# Schematic_v72.net
KiCad netlist of a schematic drawn in EAGLE
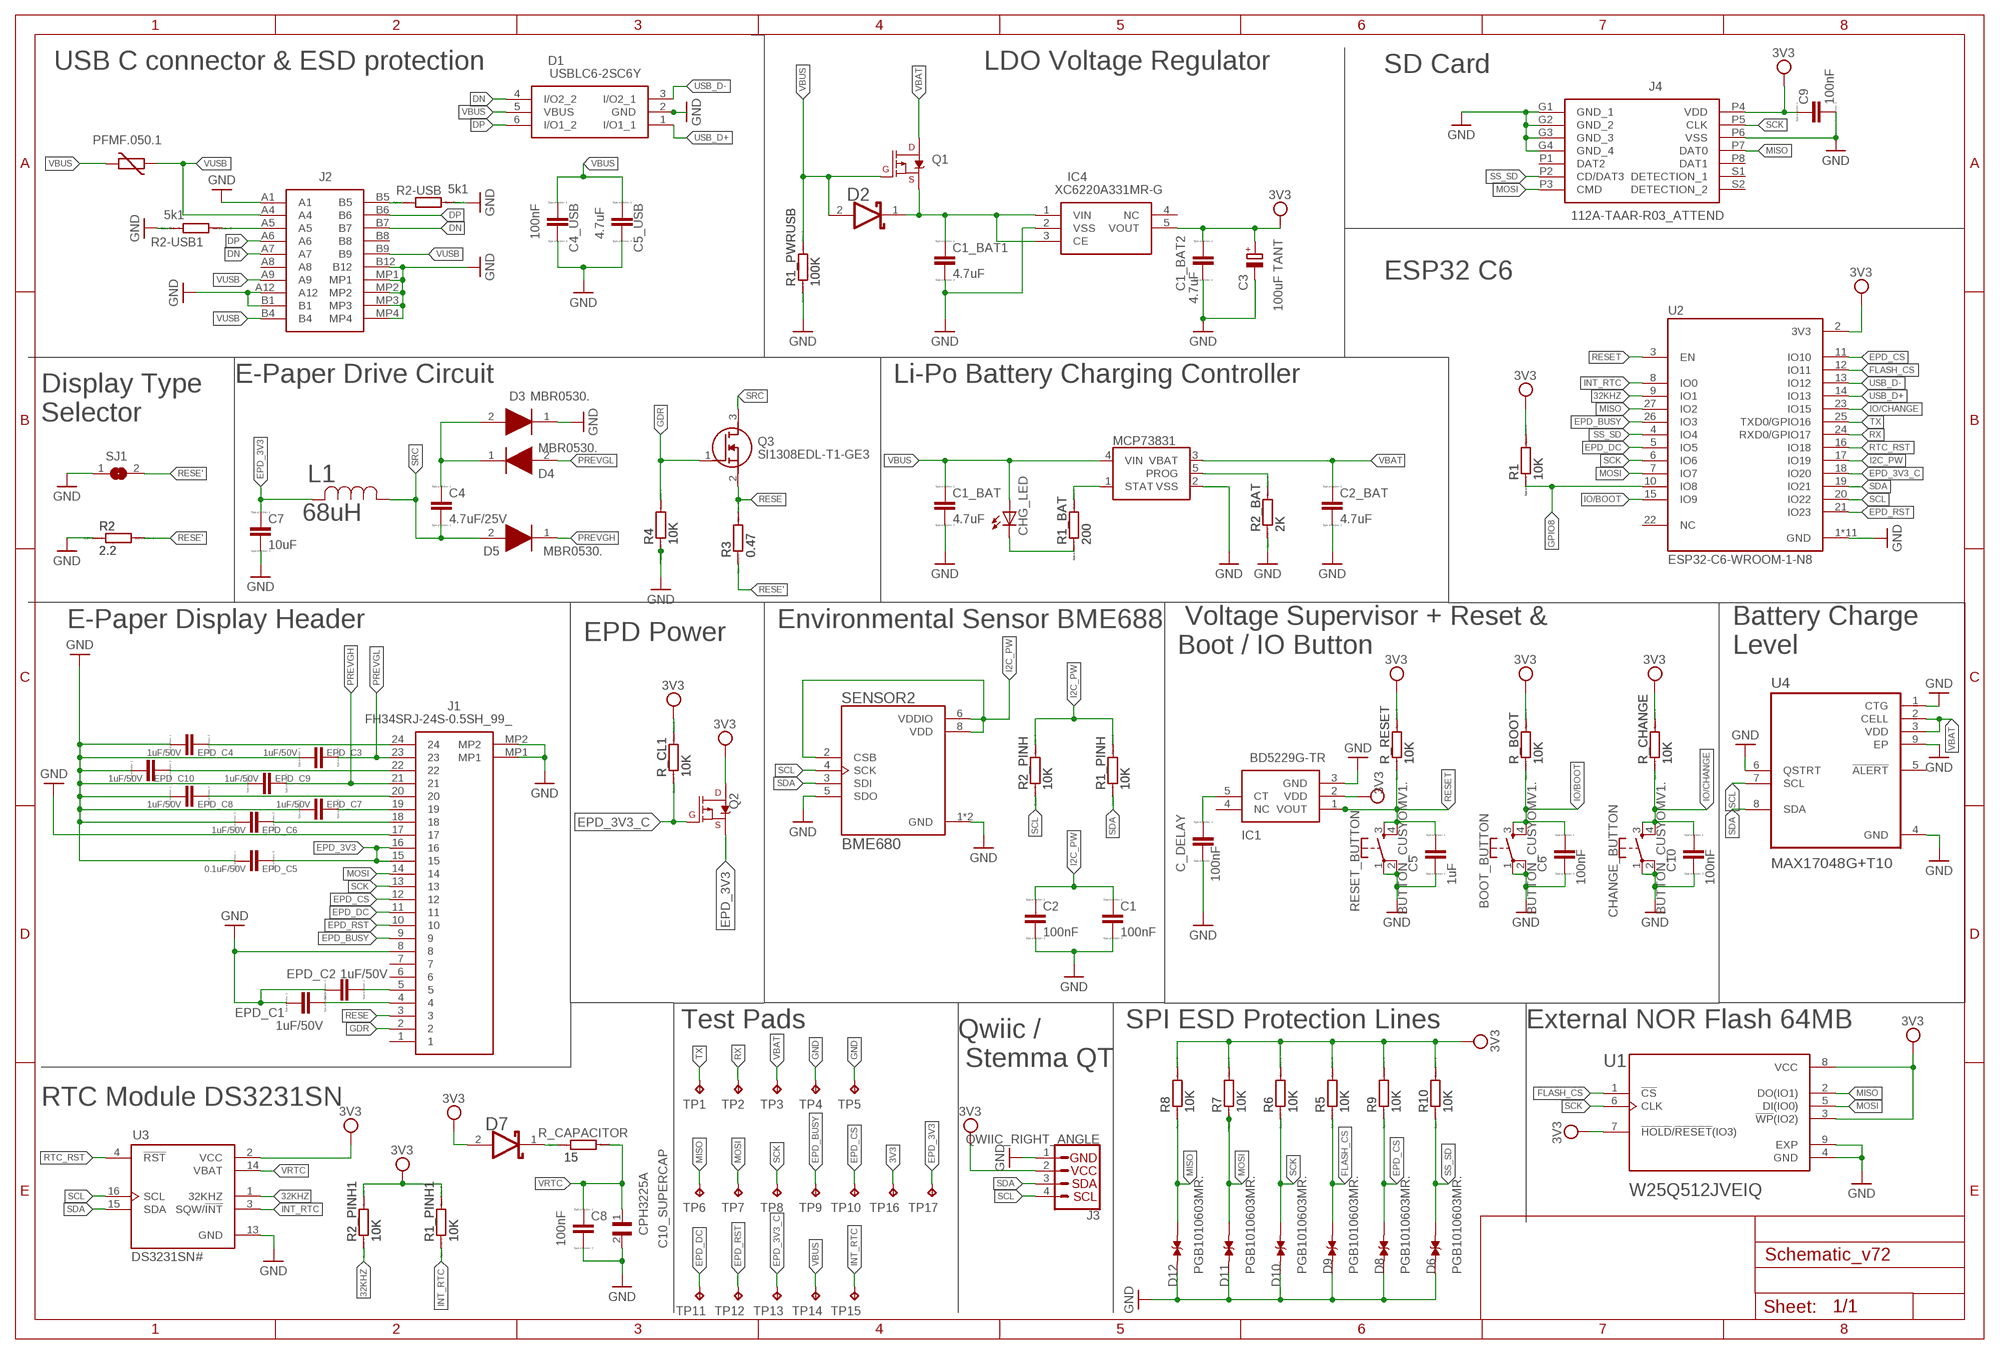
[diagram p0: schematic, sheet 1]

(export (version "E")
  (design (tool "Eeschema 10.0.6"))
  (components
    (comp (ref "BOOT_BUTTON")
      (value "BUTTON_CUSYOMV1.")
      (footprint "eagle-import:MYBUTTON")
      (libsource (lib "eagle-import") (part "BUTTON_CUSYOMV1."))
    )
    (comp (ref "C1")
      (value "100nF")
      (footprint "eagle-import:EAGLE-LTSPICE_C0402")
      (libsource (lib "eagle-import") (part "EAGLE-LTSPICE_C"))
    )
    (comp (ref "C1_BAT")
      (value "4.7uF")
      (footprint "eagle-import:EAGLE-LTSPICE_C0402")
      (libsource (lib "eagle-import") (part "EAGLE-LTSPICE_C"))
    )
    (comp (ref "C1_BAT1")
      (value "4.7uF")
      (footprint "eagle-import:EAGLE-LTSPICE_C0402")
      (libsource (lib "eagle-import") (part "EAGLE-LTSPICE_C"))
    )
    (comp (ref "C1_BAT2")
      (value "4.7uF")
      (footprint "eagle-import:EAGLE-LTSPICE_C0402")
      (libsource (lib "eagle-import") (part "EAGLE-LTSPICE_C"))
    )
    (comp (ref "C2")
      (value "100nF")
      (footprint "eagle-import:EAGLE-LTSPICE_C0402")
      (libsource (lib "eagle-import") (part "EAGLE-LTSPICE_C"))
    )
    (comp (ref "C2_BAT")
      (value "4.7uF")
      (footprint "eagle-import:EAGLE-LTSPICE_C0402")
      (libsource (lib "eagle-import") (part "EAGLE-LTSPICE_C"))
    )
    (comp (ref "C3")
      (value "100uF TANT")
      (footprint "eagle-import:RCL_CT3528")
      (libsource (lib "eagle-import") (part "RCL_CPOL-EUCT3528"))
    )
    (comp (ref "C4")
      (value "4.7uF/25V")
      (footprint "eagle-import:EAGLE-LTSPICE_C0402")
      (libsource (lib "eagle-import") (part "EAGLE-LTSPICE_C"))
    )
    (comp (ref "C4_USB")
      (value "100nF")
      (footprint "eagle-import:EAGLE-LTSPICE_C0402")
      (libsource (lib "eagle-import") (part "EAGLE-LTSPICE_C"))
    )
    (comp (ref "C5")
      (value "1uF")
      (footprint "eagle-import:EAGLE-LTSPICE_C0402")
      (libsource (lib "eagle-import") (part "EAGLE-LTSPICE_C"))
    )
    (comp (ref "C5_USB")
      (value "4.7uF")
      (footprint "eagle-import:EAGLE-LTSPICE_C0402")
      (libsource (lib "eagle-import") (part "EAGLE-LTSPICE_C"))
    )
    (comp (ref "C6")
      (value "100nF")
      (footprint "eagle-import:EAGLE-LTSPICE_C0402")
      (libsource (lib "eagle-import") (part "EAGLE-LTSPICE_C"))
    )
    (comp (ref "C7")
      (value "10uF")
      (footprint "eagle-import:EAGLE-LTSPICE_C0402")
      (libsource (lib "eagle-import") (part "EAGLE-LTSPICE_C"))
    )
    (comp (ref "C8")
      (value "100nF")
      (footprint "eagle-import:EAGLE-LTSPICE_C0402")
      (libsource (lib "eagle-import") (part "EAGLE-LTSPICE_C"))
    )
    (comp (ref "C9")
      (value "100nF")
      (footprint "eagle-import:EAGLE-LTSPICE_C0402")
      (libsource (lib "eagle-import") (part "EAGLE-LTSPICE_C"))
    )
    (comp (ref "C10")
      (value "100nF")
      (footprint "eagle-import:EAGLE-LTSPICE_C0402")
      (libsource (lib "eagle-import") (part "EAGLE-LTSPICE_C"))
    )
    (comp (ref "C10_SUPERCAP")
      (value "CPH3225A")
      (footprint "eagle-import:CAPCP3225X100N")
      (fields (field (name "MF") "Seiko Instruments"))
      (libsource (lib "eagle-import") (part "CPH3225A"))
    )
    (comp (ref "CHANGE_BUTTON")
      (value "BUTTON_CUSYOMV1.")
      (footprint "eagle-import:MYBUTTON")
      (libsource (lib "eagle-import") (part "BUTTON_CUSYOMV1."))
    )
    (comp (ref "CHG_LED")
      (value "ADAFRUIT_LEDCHIP-LED0603")
      (footprint "eagle-import:ADAFRUIT_CHIP-LED0603")
      (libsource (lib "eagle-import") (part "ADAFRUIT_LEDCHIP-LED0603"))
    )
    (comp (ref "C_DELAY")
      (value "100nF")
      (footprint "eagle-import:EAGLE-LTSPICE_C0402")
      (libsource (lib "eagle-import") (part "EAGLE-LTSPICE_C"))
    )
    (comp (ref "D1")
      (value "USBLC6-2SC6Y")
      (footprint "eagle-import:SOT95P280X145-6N")
      (fields (field (name "MF") "STMicroelectronics"))
      (libsource (lib "eagle-import") (part "USBLC6-2SC6Y"))
    )
    (comp (ref "D2")
      (value "ESP32_WROVER_AVX---SD0805S020S1R0_AVX_SD0805S020S1R0_0_0")
      (footprint "eagle-import:ESP32_WROVER_AVX---SD0805S020S1R0_AVX_SD0805S020S1R0_0")
      (libsource (lib "eagle-import") (part "ESP32_WROVER_AVX---SD0805S020S1R0_AVX_SD0805S020S1R0_0_0"))
    )
    (comp (ref "D3")
      (value "MBR0530.")
      (footprint "eagle-import:SOD3716X135N")
      (libsource (lib "eagle-import") (part "MBR0530."))
    )
    (comp (ref "D4")
      (value "MBR0530.")
      (footprint "eagle-import:SOD3716X135N")
      (libsource (lib "eagle-import") (part "MBR0530."))
    )
    (comp (ref "D5")
      (value "MBR0530.")
      (footprint "eagle-import:SOD3716X135N")
      (libsource (lib "eagle-import") (part "MBR0530."))
    )
    (comp (ref "D6")
      (value "PGB1010603MR.")
      (footprint "eagle-import:DIOC1608X36N")
      (libsource (lib "eagle-import") (part "PGB1010603MR."))
    )
    (comp (ref "D7")
      (value "SD0805S020S1R0")
      (footprint "eagle-import:ESP32_WROVER_AVX---SD0805S020S1R0_AVX_SD0805S020S1R0_0")
      (libsource (lib "eagle-import") (part "ESP32_WROVER_AVX---SD0805S020S1R0_AVX_SD0805S020S1R0_0_0"))
    )
    (comp (ref "D8")
      (value "PGB1010603MR.")
      (footprint "eagle-import:DIOC1608X36N")
      (libsource (lib "eagle-import") (part "PGB1010603MR."))
    )
    (comp (ref "D9")
      (value "PGB1010603MR.")
      (footprint "eagle-import:DIOC1608X36N")
      (libsource (lib "eagle-import") (part "PGB1010603MR."))
    )
    (comp (ref "D10")
      (value "PGB1010603MR.")
      (footprint "eagle-import:DIOC1608X36N")
      (libsource (lib "eagle-import") (part "PGB1010603MR."))
    )
    (comp (ref "D11")
      (value "PGB1010603MR.")
      (footprint "eagle-import:DIOC1608X36N")
      (libsource (lib "eagle-import") (part "PGB1010603MR."))
    )
    (comp (ref "D12")
      (value "PGB1010603MR.")
      (footprint "eagle-import:DIOC1608X36N")
      (libsource (lib "eagle-import") (part "PGB1010603MR."))
    )
    (comp (ref "EPD_C1")
      (value "1uF/50V")
      (footprint "eagle-import:EAGLE-LTSPICE_C0402")
      (libsource (lib "eagle-import") (part "EAGLE-LTSPICE_C"))
    )
    (comp (ref "EPD_C2")
      (value "1uF/50V")
      (footprint "eagle-import:EAGLE-LTSPICE_C0402")
      (libsource (lib "eagle-import") (part "EAGLE-LTSPICE_C"))
    )
    (comp (ref "EPD_C3")
      (value "1uF/50V")
      (footprint "eagle-import:EAGLE-LTSPICE_C0402")
      (libsource (lib "eagle-import") (part "EAGLE-LTSPICE_C"))
    )
    (comp (ref "EPD_C4")
      (value "1uF/50V")
      (footprint "eagle-import:EAGLE-LTSPICE_C0402")
      (libsource (lib "eagle-import") (part "EAGLE-LTSPICE_C"))
    )
    (comp (ref "EPD_C5")
      (value "0.1uF/50V")
      (footprint "eagle-import:EAGLE-LTSPICE_C0402")
      (libsource (lib "eagle-import") (part "EAGLE-LTSPICE_C"))
    )
    (comp (ref "EPD_C6")
      (value "1uF/50V")
      (footprint "eagle-import:EAGLE-LTSPICE_C0402")
      (libsource (lib "eagle-import") (part "EAGLE-LTSPICE_C"))
    )
    (comp (ref "EPD_C7")
      (value "1uF/50V")
      (footprint "eagle-import:EAGLE-LTSPICE_C0402")
      (libsource (lib "eagle-import") (part "EAGLE-LTSPICE_C"))
    )
    (comp (ref "EPD_C8")
      (value "1uF/50V")
      (footprint "eagle-import:EAGLE-LTSPICE_C0402")
      (libsource (lib "eagle-import") (part "EAGLE-LTSPICE_C"))
    )
    (comp (ref "EPD_C9")
      (value "1uF/50V")
      (footprint "eagle-import:EAGLE-LTSPICE_C0402")
      (libsource (lib "eagle-import") (part "EAGLE-LTSPICE_C"))
    )
    (comp (ref "EPD_C10")
      (value "1uF/50V")
      (footprint "eagle-import:EAGLE-LTSPICE_C0402")
      (libsource (lib "eagle-import") (part "EAGLE-LTSPICE_C"))
    )
    (comp (ref "IC1")
      (value "BD5229G-TR")
      (footprint "eagle-import:SOT95P280X125-5N")
      (fields (field (name "MOUSER_PART_NUMBER") "755-BD5229G-TR"))
      (libsource (lib "eagle-import") (part "BD5229G-TR"))
    )
    (comp (ref "IC4")
      (value "XC6220A331MR-G")
      (footprint "eagle-import:SOT95P280X120-5N")
      (fields (field (name "MOUSER_PART_NUMBER") "865-XC6220A331MR-G"))
      (libsource (lib "eagle-import") (part "XC6220A331MR-G"))
    )
    (comp (ref "J1")
      (value "FH34SRJ-24S-0.5SH_99_")
      (footprint "eagle-import:FH34SRJ24S05SH99")
      (fields
        (field (name "MANUFACTURER_PART_NUMBER") "FH34SRJ-24S-0.5SH(99)")
        (field (name "MOUSER_PART_NUMBER") "798-FH34SRJ24S05SH99")
      )
      (libsource (lib "eagle-import") (part "FH34SRJ-24S-0.5SH_99_"))
    )
    (comp (ref "J2")
      (value "SAMACSYS_PARTS_USB4110-GF-A")
      (footprint "eagle-import:SAMACSYS_PARTS_USB4110GFA")
      (fields
        (field (name "MANUFACTURER_PART_NUMBER") "USB4110-GF-A")
        (field (name "MOUSER_PART_NUMBER") "640-USB4110-GF-A")
      )
      (libsource (lib "eagle-import") (part "SAMACSYS_PARTS_USB4110-GF-A"))
    )
    (comp (ref "J3")
      (value "QWIIC_RIGHT_ANGLE")
      (footprint "eagle-import:JST04_1MM_RA")
      (libsource (lib "eagle-import") (part "QWIIC_CONNECTORJS-1MM"))
    )
    (comp (ref "J4")
      (value "112A-TAAR-R03_ATTEND")
      (footprint "eagle-import:112ATAARR03ATTEND")
      (fields (field (name "MANUFACTURER_PART_NUMBER") "112A-TAAR-R03 ATTEND"))
      (libsource (lib "eagle-import") (part "112A-TAAR-R03_ATTEND"))
    )
    (comp (ref "L1")
      (value "68uH")
      (footprint "eagle-import:IND_4828-WE-TPC_WRE")
      (fields
        (field (name "MANUFACTURER_PART_NUMBER") "744043680")
        (field (name "COPYRIGHT") "Copyright (C) 2024 Ultra Librarian. All rights reserved.")
      )
      (libsource (lib "eagle-import") (part "744043680IND_4828-WE-TPC_WRE"))
    )
    (comp (ref "MCP73831")
      (value "ESP32_WROVER_SPARKFUN-IC-POWER_MCP73831")
      (footprint "eagle-import:ESP32_WROVER_SPARKFUN-IC-POWER_SOT23-5")
      (libsource (lib "eagle-import") (part "ESP32_WROVER_SPARKFUN-IC-POWER_MCP73831"))
    )
    (comp (ref "PFMF.050.1")
      (value "ESP32C6_VARISTORCN1812")
      (footprint "eagle-import:ESP32C6_VARISTOR_CT_CN1812")
      (libsource (lib "eagle-import") (part "ESP32C6_VARISTORCN1812"))
    )
    (comp (ref "Q1")
      (value "20V/4.2A/52mΩ/1.4W")
      (footprint "eagle-import:ESP32_WROVER_SPARKFUN-DISCRETESEMI_SOT23-3")
      (libsource (lib "eagle-import") (part "ESP32_WROVER_SPARKFUN-DISCRETESEMI_MOSFET_PCH"))
    )
    (comp (ref "Q2")
      (value "20V/4.2A/52mΩ/1.4W")
      (footprint "eagle-import:ESP32_WROVER_SPARKFUN-DISCRETESEMI_SOT23-3")
      (libsource (lib "eagle-import") (part "ESP32_WROVER_SPARKFUN-DISCRETESEMI_MOSFET_PCH"))
    )
    (comp (ref "Q3")
      (value "SI1308EDL-T1-GE3")
      (footprint "eagle-import:SOT65P210X110-3N")
      (fields (field (name "MF") "Vishay Siliconix"))
      (libsource (lib "eagle-import") (part "SI1308EDL-T1-GE3"))
    )
    (comp (ref "R1")
      (value "10K")
      (footprint "eagle-import:ESP32_WROVER_EAGLE-LTSPICE_R0402")
      (libsource (lib "eagle-import") (part "ESP32_WROVER_EAGLE-LTSPICE_R"))
    )
    (comp (ref "R1_BAT")
      (value "200")
      (footprint "eagle-import:ESP32_WROVER_EAGLE-LTSPICE_R0402")
      (libsource (lib "eagle-import") (part "ESP32_WROVER_EAGLE-LTSPICE_R"))
    )
    (comp (ref "R1_PINH")
      (value "10K")
      (footprint "eagle-import:ESP32_WROVER_EAGLE-LTSPICE_R0402")
      (libsource (lib "eagle-import") (part "ESP32_WROVER_EAGLE-LTSPICE_R"))
    )
    (comp (ref "R1_PINH1")
      (value "10K")
      (footprint "eagle-import:ESP32_WROVER_EAGLE-LTSPICE_R0402")
      (libsource (lib "eagle-import") (part "ESP32_WROVER_EAGLE-LTSPICE_R"))
    )
    (comp (ref "R1_PWRUSB")
      (value "100K")
      (footprint "eagle-import:ESP32_WROVER_EAGLE-LTSPICE_R0402")
      (libsource (lib "eagle-import") (part "ESP32_WROVER_EAGLE-LTSPICE_R"))
    )
    (comp (ref "R2")
      (value "2.2")
      (footprint "eagle-import:ESP32_WROVER_EAGLE-LTSPICE_R0402")
      (libsource (lib "eagle-import") (part "ESP32_WROVER_EAGLE-LTSPICE_R"))
    )
    (comp (ref "R2-USB")
      (value "5k1")
      (footprint "eagle-import:ESP32_WROVER_EAGLE-LTSPICE_R0402")
      (libsource (lib "eagle-import") (part "ESP32_WROVER_EAGLE-LTSPICE_R"))
    )
    (comp (ref "R2-USB1")
      (value "5k1")
      (footprint "eagle-import:ESP32_WROVER_EAGLE-LTSPICE_R0402")
      (libsource (lib "eagle-import") (part "ESP32_WROVER_EAGLE-LTSPICE_R"))
    )
    (comp (ref "R2_BAT")
      (value "2K")
      (footprint "eagle-import:ESP32_WROVER_EAGLE-LTSPICE_R0402")
      (libsource (lib "eagle-import") (part "ESP32_WROVER_EAGLE-LTSPICE_R"))
    )
    (comp (ref "R2_PINH")
      (value "10K")
      (footprint "eagle-import:ESP32_WROVER_EAGLE-LTSPICE_R0402")
      (libsource (lib "eagle-import") (part "ESP32_WROVER_EAGLE-LTSPICE_R"))
    )
    (comp (ref "R2_PINH1")
      (value "10K")
      (footprint "eagle-import:ESP32_WROVER_EAGLE-LTSPICE_R0402")
      (libsource (lib "eagle-import") (part "ESP32_WROVER_EAGLE-LTSPICE_R"))
    )
    (comp (ref "R3")
      (value "0.47")
      (footprint "eagle-import:ESP32_WROVER_EAGLE-LTSPICE_R0402")
      (libsource (lib "eagle-import") (part "ESP32_WROVER_EAGLE-LTSPICE_R"))
    )
    (comp (ref "R4")
      (value "10K")
      (footprint "eagle-import:ESP32_WROVER_EAGLE-LTSPICE_R0402")
      (libsource (lib "eagle-import") (part "ESP32_WROVER_EAGLE-LTSPICE_R"))
    )
    (comp (ref "R5")
      (value "10K")
      (footprint "eagle-import:ESP32_WROVER_EAGLE-LTSPICE_R0402")
      (libsource (lib "eagle-import") (part "ESP32_WROVER_EAGLE-LTSPICE_R"))
    )
    (comp (ref "R6")
      (value "10K")
      (footprint "eagle-import:ESP32_WROVER_EAGLE-LTSPICE_R0402")
      (libsource (lib "eagle-import") (part "ESP32_WROVER_EAGLE-LTSPICE_R"))
    )
    (comp (ref "R7")
      (value "10K")
      (footprint "eagle-import:ESP32_WROVER_EAGLE-LTSPICE_R0402")
      (libsource (lib "eagle-import") (part "ESP32_WROVER_EAGLE-LTSPICE_R"))
    )
    (comp (ref "R8")
      (value "10K")
      (footprint "eagle-import:ESP32_WROVER_EAGLE-LTSPICE_R0402")
      (libsource (lib "eagle-import") (part "ESP32_WROVER_EAGLE-LTSPICE_R"))
    )
    (comp (ref "R9")
      (value "10K")
      (footprint "eagle-import:ESP32_WROVER_EAGLE-LTSPICE_R0402")
      (libsource (lib "eagle-import") (part "ESP32_WROVER_EAGLE-LTSPICE_R"))
    )
    (comp (ref "R10")
      (value "10K")
      (footprint "eagle-import:ESP32_WROVER_EAGLE-LTSPICE_R0402")
      (libsource (lib "eagle-import") (part "ESP32_WROVER_EAGLE-LTSPICE_R"))
    )
    (comp (ref "RESET_BUTTON")
      (value "BUTTON_CUSYOMV1.")
      (footprint "eagle-import:MYBUTTON")
      (libsource (lib "eagle-import") (part "BUTTON_CUSYOMV1."))
    )
    (comp (ref "R_BOOT")
      (value "10K")
      (footprint "eagle-import:ESP32_WROVER_EAGLE-LTSPICE_R0402")
      (libsource (lib "eagle-import") (part "ESP32_WROVER_EAGLE-LTSPICE_R"))
    )
    (comp (ref "R_CAPACITOR")
      (value "15")
      (footprint "eagle-import:ESP32_WROVER_EAGLE-LTSPICE_R0402")
      (libsource (lib "eagle-import") (part "ESP32_WROVER_EAGLE-LTSPICE_R"))
    )
    (comp (ref "R_CHANGE")
      (value "10K")
      (footprint "eagle-import:ESP32_WROVER_EAGLE-LTSPICE_R0402")
      (libsource (lib "eagle-import") (part "ESP32_WROVER_EAGLE-LTSPICE_R"))
    )
    (comp (ref "R_CL1")
      (value "10K")
      (footprint "eagle-import:ESP32_WROVER_EAGLE-LTSPICE_R0402")
      (libsource (lib "eagle-import") (part "ESP32_WROVER_EAGLE-LTSPICE_R"))
    )
    (comp (ref "R_RESET")
      (value "10K")
      (footprint "eagle-import:ESP32_WROVER_EAGLE-LTSPICE_R0402")
      (libsource (lib "eagle-import") (part "ESP32_WROVER_EAGLE-LTSPICE_R"))
    )
    (comp (ref "SENSOR2")
      (value "BME680")
      (footprint "eagle-import:ESP32_WROVER_BME680_PSON80P300X300X100-8N")
      (fields (field (name "MF") "Bosch Sensortec"))
      (libsource (lib "eagle-import") (part "ESP32_WROVER_BME680_BME680"))
    )
    (comp (ref "SJ1") (value "SJ") (footprint "eagle-import:SJ") (libsource (lib "eagle-import") (part "SJ")))
    (comp (ref "TP1")
      (value "TX")
      (footprint "eagle-import:TP20R")
      (libsource (lib "eagle-import") (part "TP"))
    )
    (comp (ref "TP2")
      (value "RX")
      (footprint "eagle-import:TP20R")
      (libsource (lib "eagle-import") (part "TP"))
    )
    (comp (ref "TP3")
      (value "VBAT")
      (footprint "eagle-import:TP20R")
      (libsource (lib "eagle-import") (part "TP"))
    )
    (comp (ref "TP4")
      (value "GND")
      (footprint "eagle-import:TP20R")
      (libsource (lib "eagle-import") (part "TP"))
    )
    (comp (ref "TP5")
      (value "GND")
      (footprint "eagle-import:TP20R")
      (libsource (lib "eagle-import") (part "TP"))
    )
    (comp (ref "TP6")
      (value "MISO")
      (footprint "eagle-import:TP20R")
      (libsource (lib "eagle-import") (part "TP"))
    )
    (comp (ref "TP7")
      (value "MOSI")
      (footprint "eagle-import:TP20R")
      (libsource (lib "eagle-import") (part "TP"))
    )
    (comp (ref "TP8")
      (value "SCK")
      (footprint "eagle-import:TP20R")
      (libsource (lib "eagle-import") (part "TP"))
    )
    (comp (ref "TP9")
      (value "EPD_BUSY")
      (footprint "eagle-import:TP20R")
      (libsource (lib "eagle-import") (part "TP"))
    )
    (comp (ref "TP10")
      (value "EPD_CS")
      (footprint "eagle-import:TP20R")
      (libsource (lib "eagle-import") (part "TP"))
    )
    (comp (ref "TP11")
      (value "EPD_DC")
      (footprint "eagle-import:TP20R")
      (libsource (lib "eagle-import") (part "TP"))
    )
    (comp (ref "TP12")
      (value "EPD_RST")
      (footprint "eagle-import:TP20R")
      (libsource (lib "eagle-import") (part "TP"))
    )
    (comp (ref "TP13")
      (value "EPD_3V3_C")
      (footprint "eagle-import:TP20R")
      (libsource (lib "eagle-import") (part "TP"))
    )
    (comp (ref "TP14")
      (value "VBUS")
      (footprint "eagle-import:TP20R")
      (libsource (lib "eagle-import") (part "TP"))
    )
    (comp (ref "TP15")
      (value "INT_RTC")
      (footprint "eagle-import:TP20R")
      (libsource (lib "eagle-import") (part "TP"))
    )
    (comp (ref "TP16")
      (value "3V3")
      (footprint "eagle-import:TP20R")
      (libsource (lib "eagle-import") (part "TP"))
    )
    (comp (ref "TP17")
      (value "EPD_3V3")
      (footprint "eagle-import:TP20R")
      (libsource (lib "eagle-import") (part "TP"))
    )
    (comp (ref "U1")
      (value "W25Q512JVEIQ")
      (footprint "eagle-import:SON127P600X800X80-9N")
      (fields (field (name "MF") "Winbond Electronics"))
      (libsource (lib "eagle-import") (part "W25Q512JVEIQ"))
    )
    (comp (ref "U2")
      (value "ESP32-C6-WROOM-1-N8")
      (footprint "eagle-import:XCVR_ESP32-C6-WROOM-1-N8")
      (fields (field (name "MF") "Espressif Systems"))
      (libsource (lib "eagle-import") (part "ESP32-C6-WROOM-1-N8"))
    )
    (comp (ref "U3")
      (value "DS3231SN#")
      (footprint "eagle-import:SOIC127P1032X265-16N")
      (fields (field (name "MF") "Analog Devices"))
      (libsource (lib "eagle-import") (part "DS3231SN#"))
    )
    (comp (ref "U4")
      (value "MAX17048G+T10")
      (footprint "eagle-import:SON50P200X200X80-9N")
      (fields (field (name "MF") "Analog Devices"))
      (libsource (lib "eagle-import") (part "MAX17048G+T10"))
    )
  )
  (nets
    (net (code "1") (name "3V3") (class "Default")
      (node (ref "C1_BAT2") (pin "1") (pinfunction "1_1") (pintype "passive"))
      (node (ref "C3") (pin "+") (pinfunction "+_+") (pintype "passive"))
      (node (ref "C9") (pin "1") (pinfunction "1_1") (pintype "passive"))
      (node (ref "D7") (pin "2") (pinfunction "ANODE_2") (pintype "bidirectional"))
      (node (ref "IC1") (pin "2") (pinfunction "VDD_2") (pintype "bidirectional"))
      (node (ref "IC4") (pin "5") (pinfunction "VOUT_5") (pintype "bidirectional"))
      (node (ref "J3") (pin "2") (pinfunction "2_2") (pintype "power_in"))
      (node (ref "J4") (pin "P4") (pinfunction "VDD_P4") (pintype "bidirectional"))
      (node (ref "Q2") (pin "3") (pinfunction "D_3") (pintype "bidirectional"))
      (node (ref "R1") (pin "2") (pinfunction "2_2") (pintype "passive"))
      (node (ref "R10") (pin "2") (pinfunction "2_2") (pintype "passive"))
      (node (ref "R1_PINH1") (pin "2") (pinfunction "2_2") (pintype "passive"))
      (node (ref "R2_PINH1") (pin "2") (pinfunction "2_2") (pintype "passive"))
      (node (ref "R5") (pin "2") (pinfunction "2_2") (pintype "passive"))
      (node (ref "R6") (pin "2") (pinfunction "2_2") (pintype "passive"))
      (node (ref "R7") (pin "2") (pinfunction "2_2") (pintype "passive"))
      (node (ref "R8") (pin "2") (pinfunction "2_2") (pintype "passive"))
      (node (ref "R9") (pin "2") (pinfunction "2_2") (pintype "passive"))
      (node (ref "R_BOOT") (pin "2") (pinfunction "2_2") (pintype "passive"))
      (node (ref "R_CHANGE") (pin "2") (pinfunction "2_2") (pintype "passive"))
      (node (ref "R_CL1") (pin "2") (pinfunction "2_2") (pintype "passive"))
      (node (ref "R_RESET") (pin "2") (pinfunction "2_2") (pintype "passive"))
      (node (ref "TP16") (pin "TP") (pinfunction "TP_TP") (pintype "input"))
      (node (ref "U1") (pin "3") (pinfunction "~{WP}(IO2)_3") (pintype "bidirectional"))
      (node (ref "U1") (pin "7") (pinfunction "~{HOLD}/~{RESET}(IO3)_7") (pintype "bidirectional"))
      (node (ref "U1") (pin "8") (pinfunction "VCC_8") (pintype "power_in"))
      (node (ref "U2") (pin "2") (pinfunction "3V3_2") (pintype "power_in"))
      (node (ref "U3") (pin "2") (pinfunction "VCC_2") (pintype "power_in"))
    )
    (net (code "2") (name "32KHZ") (class "Default")
      (node (ref "R2_PINH1") (pin "1") (pinfunction "1_1") (pintype "passive"))
      (node (ref "U2") (pin "9") (pinfunction "IO1_9") (pintype "bidirectional"))
      (node (ref "U3") (pin "1") (pinfunction "32KHZ_1") (pintype "output"))
    )
    (net (code "3") (name "DN") (class "Default")
      (node (ref "D1") (pin "4") (pinfunction "I/O2_2_4") (pintype "bidirectional"))
      (node (ref "J2") (pin "A7") (pinfunction "A7_A7") (pintype "bidirectional"))
      (node (ref "J2") (pin "B7") (pinfunction "B7_B7") (pintype "bidirectional"))
    )
    (net (code "4") (name "DP") (class "Default")
      (node (ref "D1") (pin "6") (pinfunction "I/O1_2_6") (pintype "bidirectional"))
      (node (ref "J2") (pin "A6") (pinfunction "A6_A6") (pintype "bidirectional"))
      (node (ref "J2") (pin "B6") (pinfunction "B6_B6") (pintype "bidirectional"))
    )
    (net (code "5") (name "EPD_3V3") (class "Default")
      (node (ref "C7") (pin "1") (pinfunction "1_1") (pintype "passive"))
      (node (ref "EPD_C5") (pin "2") (pinfunction "2_2") (pintype "passive"))
      (node (ref "J1") (pin "15") (pinfunction "15_15") (pintype "bidirectional"))
      (node (ref "J1") (pin "16") (pinfunction "16_16") (pintype "bidirectional"))
      (node (ref "L1") (pin "2") (pinfunction "2_2") (pintype "passive"))
      (node (ref "Q2") (pin "2") (pinfunction "S_2") (pintype "bidirectional"))
      (node (ref "TP17") (pin "TP") (pinfunction "TP_TP") (pintype "input"))
    )
    (net (code "6") (name "EPD_3V3_C") (class "Default")
      (node (ref "Q2") (pin "1") (pinfunction "G_1") (pintype "bidirectional"))
      (node (ref "R_CL1") (pin "1") (pinfunction "1_1") (pintype "passive"))
      (node (ref "TP13") (pin "TP") (pinfunction "TP_TP") (pintype "input"))
      (node (ref "U2") (pin "18") (pinfunction "IO20_18") (pintype "bidirectional"))
    )
    (net (code "7") (name "EPD_BUSY") (class "Default")
      (node (ref "J1") (pin "9") (pinfunction "9_9") (pintype "bidirectional"))
      (node (ref "TP9") (pin "TP") (pinfunction "TP_TP") (pintype "input"))
      (node (ref "U2") (pin "26") (pinfunction "IO3_26") (pintype "bidirectional"))
    )
    (net (code "8") (name "EPD_CS") (class "Default")
      (node (ref "D8") (pin "2") (pinfunction "2_2") (pintype "passive"))
      (node (ref "J1") (pin "12") (pinfunction "12_12") (pintype "bidirectional"))
      (node (ref "R9") (pin "1") (pinfunction "1_1") (pintype "passive"))
      (node (ref "TP10") (pin "TP") (pinfunction "TP_TP") (pintype "input"))
      (node (ref "U2") (pin "11") (pinfunction "IO10_11") (pintype "bidirectional"))
    )
    (net (code "9") (name "EPD_DC") (class "Default")
      (node (ref "J1") (pin "11") (pinfunction "11_11") (pintype "bidirectional"))
      (node (ref "TP11") (pin "TP") (pinfunction "TP_TP") (pintype "input"))
      (node (ref "U2") (pin "5") (pinfunction "IO5_5") (pintype "bidirectional"))
    )
    (net (code "10") (name "EPD_RST") (class "Default")
      (node (ref "J1") (pin "10") (pinfunction "10_10") (pintype "bidirectional"))
      (node (ref "TP12") (pin "TP") (pinfunction "TP_TP") (pintype "input"))
      (node (ref "U2") (pin "21") (pinfunction "IO23_21") (pintype "bidirectional"))
    )
    (net (code "11") (name "FLASH_CS") (class "Default")
      (node (ref "D9") (pin "2") (pinfunction "2_2") (pintype "passive"))
      (node (ref "R5") (pin "1") (pinfunction "1_1") (pintype "passive"))
      (node (ref "U1") (pin "1") (pinfunction "~{CS}_1") (pintype "input"))
      (node (ref "U2") (pin "12") (pinfunction "IO11_12") (pintype "bidirectional"))
    )
    (net (code "12") (name "GDR") (class "Default")
      (node (ref "J1") (pin "2") (pinfunction "2_2") (pintype "bidirectional"))
      (node (ref "Q3") (pin "1") (pinfunction "G_1") (pintype "bidirectional"))
      (node (ref "R4") (pin "2") (pinfunction "2_2") (pintype "passive"))
    )
    (net (code "13") (name "GND") (class "Default")
      (node (ref "BOOT_BUTTON") (pin "1") (pinfunction "1_1") (pintype "passive"))
      (node (ref "BOOT_BUTTON") (pin "2") (pinfunction "2_2") (pintype "passive"))
      (node (ref "C1") (pin "2") (pinfunction "2_2") (pintype "passive"))
      (node (ref "C10") (pin "2") (pinfunction "2_2") (pintype "passive"))
      (node (ref "C10_SUPERCAP") (pin "2") (pinfunction "2_2") (pintype "passive"))
      (node (ref "C1_BAT") (pin "2") (pinfunction "2_2") (pintype "passive"))
      (node (ref "C1_BAT1") (pin "2") (pinfunction "2_2") (pintype "passive"))
      (node (ref "C1_BAT2") (pin "2") (pinfunction "2_2") (pintype "passive"))
      (node (ref "C2") (pin "2") (pinfunction "2_2") (pintype "passive"))
      (node (ref "C2_BAT") (pin "2") (pinfunction "2_2") (pintype "passive"))
      (node (ref "C3") (pin "-") (pinfunction "-_-") (pintype "passive"))
      (node (ref "C4_USB") (pin "2") (pinfunction "2_2") (pintype "passive"))
      (node (ref "C5") (pin "2") (pinfunction "2_2") (pintype "passive"))
      (node (ref "C5_USB") (pin "2") (pinfunction "2_2") (pintype "passive"))
      (node (ref "C6") (pin "2") (pinfunction "2_2") (pintype "passive"))
      (node (ref "C7") (pin "2") (pinfunction "2_2") (pintype "passive"))
      (node (ref "C8") (pin "2") (pinfunction "2_2") (pintype "passive"))
      (node (ref "C9") (pin "2") (pinfunction "2_2") (pintype "passive"))
      (node (ref "CHANGE_BUTTON") (pin "1") (pinfunction "1_1") (pintype "passive"))
      (node (ref "CHANGE_BUTTON") (pin "2") (pinfunction "2_2") (pintype "passive"))
      (node (ref "C_DELAY") (pin "2") (pinfunction "2_2") (pintype "passive"))
      (node (ref "D1") (pin "2") (pinfunction "GND_2") (pintype "bidirectional"))
      (node (ref "D10") (pin "1") (pinfunction "1_1") (pintype "passive"))
      (node (ref "D11") (pin "1") (pinfunction "1_1") (pintype "passive"))
      (node (ref "D12") (pin "1") (pinfunction "1_1") (pintype "passive"))
      (node (ref "D3") (pin "1") (pinfunction "K_1") (pintype "bidirectional"))
      (node (ref "D6") (pin "1") (pinfunction "1_1") (pintype "passive"))
      (node (ref "D8") (pin "1") (pinfunction "1_1") (pintype "passive"))
      (node (ref "D9") (pin "1") (pinfunction "1_1") (pintype "passive"))
      (node (ref "EPD_C1") (pin "1") (pinfunction "1_1") (pintype "passive"))
      (node (ref "EPD_C10") (pin "1") (pinfunction "1_1") (pintype "passive"))
      (node (ref "EPD_C2") (pin "1") (pinfunction "1_1") (pintype "passive"))
      (node (ref "EPD_C3") (pin "1") (pinfunction "1_1") (pintype "passive"))
      (node (ref "EPD_C4") (pin "1") (pinfunction "1_1") (pintype "passive"))
      (node (ref "EPD_C5") (pin "1") (pinfunction "1_1") (pintype "passive"))
      (node (ref "EPD_C6") (pin "1") (pinfunction "1_1") (pintype "passive"))
      (node (ref "EPD_C7") (pin "1") (pinfunction "1_1") (pintype "passive"))
      (node (ref "EPD_C8") (pin "1") (pinfunction "1_1") (pintype "passive"))
      (node (ref "EPD_C9") (pin "1") (pinfunction "1_1") (pintype "passive"))
      (node (ref "IC1") (pin "3") (pinfunction "GND_3") (pintype "bidirectional"))
      (node (ref "IC4") (pin "2") (pinfunction "VSS_2") (pintype "bidirectional"))
      (node (ref "J1") (pin "17") (pinfunction "17_17") (pintype "bidirectional"))
      (node (ref "J1") (pin "8") (pinfunction "8_8") (pintype "bidirectional"))
      (node (ref "J1") (pin "MP1") (pinfunction "MP1_MP1") (pintype "bidirectional"))
      (node (ref "J1") (pin "MP2") (pinfunction "MP2_MP2") (pintype "bidirectional"))
      (node (ref "J2") (pin "A1") (pinfunction "A1_A1") (pintype "bidirectional"))
      (node (ref "J2") (pin "A12") (pinfunction "A12_A12") (pintype "bidirectional"))
      (node (ref "J2") (pin "B1") (pinfunction "B1_B1") (pintype "bidirectional"))
      (node (ref "J2") (pin "B12") (pinfunction "B12_B12") (pintype "bidirectional"))
      (node (ref "J2") (pin "MP1") (pinfunction "MP1_MP1") (pintype "bidirectional"))
      (node (ref "J2") (pin "MP2") (pinfunction "MP2_MP2") (pintype "bidirectional"))
      (node (ref "J2") (pin "MP3") (pinfunction "MP3_MP3") (pintype "bidirectional"))
      (node (ref "J2") (pin "MP4") (pinfunction "MP4_MP4") (pintype "bidirectional"))
      (node (ref "J3") (pin "1") (pinfunction "1_1") (pintype "power_in"))
      (node (ref "J4") (pin "G1") (pinfunction "GND_1_G1") (pintype "bidirectional"))
      (node (ref "J4") (pin "G2") (pinfunction "GND_2_G2") (pintype "bidirectional"))
      (node (ref "J4") (pin "G3") (pinfunction "GND_3_G3") (pintype "bidirectional"))
      (node (ref "J4") (pin "G4") (pinfunction "GND_4_G4") (pintype "bidirectional"))
      (node (ref "J4") (pin "P6") (pinfunction "VSS_P6") (pintype "bidirectional"))
      (node (ref "MCP73831") (pin "2") (pinfunction "VSS_2") (pintype "power_in"))
      (node (ref "R1_PWRUSB") (pin "1") (pinfunction "1_1") (pintype "passive"))
      (node (ref "R2") (pin "1") (pinfunction "1_1") (pintype "passive"))
      (node (ref "R2-USB") (pin "2") (pinfunction "2_2") (pintype "passive"))
      (node (ref "R2-USB1") (pin "1") (pinfunction "1_1") (pintype "passive"))
      (node (ref "R2_BAT") (pin "1") (pinfunction "1_1") (pintype "passive"))
      (node (ref "R4") (pin "1") (pinfunction "1_1") (pintype "passive"))
      (node (ref "RESET_BUTTON") (pin "1") (pinfunction "1_1") (pintype "passive"))
      (node (ref "RESET_BUTTON") (pin "2") (pinfunction "2_2") (pintype "passive"))
      (node (ref "SENSOR2") (pin "1") (pinfunction "GND_1") (pintype "power_in"))
      (node (ref "SENSOR2") (pin "5") (pinfunction "SDO_5") (pintype "bidirectional"))
      (node (ref "SENSOR2") (pin "7") (pinfunction "GND_7") (pintype "power_in"))
      (node (ref "SJ1") (pin "1") (pinfunction "1_1") (pintype "passive"))
      (node (ref "TP4") (pin "TP") (pinfunction "TP_TP") (pintype "input"))
      (node (ref "TP5") (pin "TP") (pinfunction "TP_TP") (pintype "input"))
      (node (ref "U1") (pin "4") (pinfunction "GND_4") (pintype "power_in"))
      (node (ref "U1") (pin "9") (pinfunction "EXP_9") (pintype "passive"))
      (node (ref "U2") (pin "1") (pinfunction "GND_1") (pintype "power_in"))
      (node (ref "U2") (pin "28") (pinfunction "GND_28") (pintype "power_in"))
      (node (ref "U2") (pin "29_1") (pinfunction "GND_29_1") (pintype "power_in"))
      (node (ref "U2") (pin "29_2") (pinfunction "GND_29_2") (pintype "power_in"))
      (node (ref "U2") (pin "29_3") (pinfunction "GND_29_3") (pintype "power_in"))
      (node (ref "U2") (pin "29_4") (pinfunction "GND_29_4") (pintype "power_in"))
      (node (ref "U2") (pin "29_5") (pinfunction "GND_29_5") (pintype "power_in"))
      (node (ref "U2") (pin "29_6") (pinfunction "GND_29_6") (pintype "power_in"))
      (node (ref "U2") (pin "29_7") (pinfunction "GND_29_7") (pintype "power_in"))
      (node (ref "U2") (pin "29_8") (pinfunction "GND_29_8") (pintype "power_in"))
      (node (ref "U2") (pin "29_9") (pinfunction "GND_29_9") (pintype "power_in"))
      (node (ref "U3") (pin "13") (pinfunction "GND_13") (pintype "power_in"))
      (node (ref "U4") (pin "1") (pinfunction "CTG_1") (pintype "power_in"))
      (node (ref "U4") (pin "4") (pinfunction "GND_4") (pintype "power_in"))
      (node (ref "U4") (pin "6") (pinfunction "QSTRT_6") (pintype "input"))
      (node (ref "U4") (pin "9") (pinfunction "EP_9") (pintype "power_in"))
    )
    (net (code "14") (name "GPIO8") (class "Default")
      (node (ref "R1") (pin "1") (pinfunction "1_1") (pintype "passive"))
      (node (ref "U2") (pin "10") (pinfunction "IO8_10") (pintype "bidirectional"))
    )
    (net (code "15") (name "I2C_PW") (class "Default")
      (node (ref "C1") (pin "1") (pinfunction "1_1") (pintype "passive"))
      (node (ref "C2") (pin "1") (pinfunction "1_1") (pintype "passive"))
      (node (ref "R1_PINH") (pin "2") (pinfunction "2_2") (pintype "passive"))
      (node (ref "R2_PINH") (pin "2") (pinfunction "2_2") (pintype "passive"))
      (node (ref "SENSOR2") (pin "2") (pinfunction "CSB_2") (pintype "input"))
      (node (ref "SENSOR2") (pin "6") (pinfunction "VDDIO_6") (pintype "power_in"))
      (node (ref "SENSOR2") (pin "8") (pinfunction "VDD_8") (pintype "power_in"))
      (node (ref "U2") (pin "17") (pinfunction "IO19_17") (pintype "bidirectional"))
    )
    (net (code "16") (name "INT_RTC") (class "Default")
      (node (ref "R1_PINH1") (pin "1") (pinfunction "1_1") (pintype "passive"))
      (node (ref "TP15") (pin "TP") (pinfunction "TP_TP") (pintype "input"))
      (node (ref "U2") (pin "8") (pinfunction "IO0_8") (pintype "bidirectional"))
      (node (ref "U3") (pin "3") (pinfunction "SQW/~{INT}_3") (pintype "output"))
    )
    (net (code "17") (name "IO{slash}BOOT") (class "Default")
      (node (ref "BOOT_BUTTON") (pin "3") (pinfunction "3_3") (pintype "passive"))
      (node (ref "BOOT_BUTTON") (pin "4") (pinfunction "4_4") (pintype "passive"))
      (node (ref "C6") (pin "1") (pinfunction "1_1") (pintype "passive"))
      (node (ref "R_BOOT") (pin "1") (pinfunction "1_1") (pintype "passive"))
      (node (ref "U2") (pin "15") (pinfunction "IO9_15") (pintype "bidirectional"))
    )
    (net (code "18") (name "IO{slash}CHANGE") (class "Default")
      (node (ref "C10") (pin "1") (pinfunction "1_1") (pintype "passive"))
      (node (ref "CHANGE_BUTTON") (pin "3") (pinfunction "3_3") (pintype "passive"))
      (node (ref "CHANGE_BUTTON") (pin "4") (pinfunction "4_4") (pintype "passive"))
      (node (ref "R_CHANGE") (pin "1") (pinfunction "1_1") (pintype "passive"))
      (node (ref "U2") (pin "23") (pinfunction "IO15_23") (pintype "bidirectional"))
    )
    (net (code "19") (name "MISO") (class "Default")
      (node (ref "D12") (pin "2") (pinfunction "2_2") (pintype "passive"))
      (node (ref "J4") (pin "P7") (pinfunction "DAT0_P7") (pintype "bidirectional"))
      (node (ref "R8") (pin "1") (pinfunction "1_1") (pintype "passive"))
      (node (ref "TP6") (pin "TP") (pinfunction "TP_TP") (pintype "input"))
      (node (ref "U1") (pin "2") (pinfunction "DO(IO1)_2") (pintype "bidirectional"))
      (node (ref "U2") (pin "27") (pinfunction "IO2_27") (pintype "bidirectional"))
    )
    (net (code "20") (name "MOSI") (class "Default")
      (node (ref "D11") (pin "2") (pinfunction "2_2") (pintype "passive"))
      (node (ref "J1") (pin "14") (pinfunction "14_14") (pintype "bidirectional"))
      (node (ref "J4") (pin "P3") (pinfunction "CMD_P3") (pintype "bidirectional"))
      (node (ref "R7") (pin "1") (pinfunction "1_1") (pintype "passive"))
      (node (ref "TP7") (pin "TP") (pinfunction "TP_TP") (pintype "input"))
      (node (ref "U1") (pin "5") (pinfunction "DI(IO0)_5") (pintype "bidirectional"))
      (node (ref "U2") (pin "7") (pinfunction "IO7_7") (pintype "bidirectional"))
    )
    (net (code "21") (name "Net-(CHG_LED-PadC)") (class "Default")
      (node (ref "CHG_LED") (pin "C") (pinfunction "C_C") (pintype "passive"))
      (node (ref "R1_BAT") (pin "1") (pinfunction "1_1") (pintype "passive"))
    )
    (net (code "22") (name "Net-(D2-CATHODE)") (class "Default")
      (node (ref "C1_BAT1") (pin "1") (pinfunction "1_1") (pintype "passive"))
      (node (ref "D2") (pin "1") (pinfunction "CATHODE_1") (pintype "bidirectional"))
      (node (ref "IC4") (pin "1") (pinfunction "VIN_1") (pintype "bidirectional"))
      (node (ref "IC4") (pin "3") (pinfunction "CE_3") (pintype "bidirectional"))
      (node (ref "Q1") (pin "2") (pinfunction "S_2") (pintype "bidirectional"))
    )
    (net (code "23") (name "Net-(D3-A)") (class "Default")
      (node (ref "C4") (pin "1") (pinfunction "1_1") (pintype "passive"))
      (node (ref "D3") (pin "2") (pinfunction "A_2") (pintype "bidirectional"))
      (node (ref "D4") (pin "1") (pinfunction "K_1") (pintype "bidirectional"))
    )
    (net (code "24") (name "Net-(D7-CATHODE)") (class "Default")
      (node (ref "D7") (pin "1") (pinfunction "CATHODE_1") (pintype "bidirectional"))
      (node (ref "R_CAPACITOR") (pin "1") (pinfunction "1_1") (pintype "passive"))
    )
    (net (code "25") (name "Net-(EPD_C1-Pad2)") (class "Default")
      (node (ref "EPD_C1") (pin "2") (pinfunction "2_2") (pintype "passive"))
      (node (ref "J1") (pin "4") (pinfunction "4_4") (pintype "bidirectional"))
    )
    (net (code "26") (name "Net-(EPD_C2-Pad2)") (class "Default")
      (node (ref "EPD_C2") (pin "2") (pinfunction "2_2") (pintype "passive"))
      (node (ref "J1") (pin "5") (pinfunction "5_5") (pintype "bidirectional"))
    )
    (net (code "27") (name "Net-(EPD_C4-Pad2)") (class "Default")
      (node (ref "EPD_C4") (pin "2") (pinfunction "2_2") (pintype "passive"))
      (node (ref "J1") (pin "24") (pinfunction "24_24") (pintype "bidirectional"))
    )
    (net (code "28") (name "Net-(EPD_C6-Pad2)") (class "Default")
      (node (ref "EPD_C6") (pin "2") (pinfunction "2_2") (pintype "passive"))
      (node (ref "J1") (pin "18") (pinfunction "18_18") (pintype "bidirectional"))
    )
    (net (code "29") (name "Net-(EPD_C7-Pad2)") (class "Default")
      (node (ref "EPD_C7") (pin "2") (pinfunction "2_2") (pintype "passive"))
      (node (ref "J1") (pin "19") (pinfunction "19_19") (pintype "bidirectional"))
    )
    (net (code "30") (name "Net-(EPD_C8-Pad2)") (class "Default")
      (node (ref "EPD_C8") (pin "2") (pinfunction "2_2") (pintype "passive"))
      (node (ref "J1") (pin "20") (pinfunction "20_20") (pintype "bidirectional"))
    )
    (net (code "31") (name "Net-(EPD_C10-Pad2)") (class "Default")
      (node (ref "EPD_C10") (pin "2") (pinfunction "2_2") (pintype "passive"))
      (node (ref "J1") (pin "22") (pinfunction "22_22") (pintype "bidirectional"))
    )
    (net (code "32") (name "Net-(IC1-CT)") (class "Default")
      (node (ref "C_DELAY") (pin "1") (pinfunction "1_1") (pintype "passive"))
      (node (ref "IC1") (pin "5") (pinfunction "CT_5") (pintype "bidirectional"))
    )
    (net (code "33") (name "Net-(J2-PadA5)") (class "Default")
      (node (ref "J2") (pin "A5") (pinfunction "A5_A5") (pintype "bidirectional"))
      (node (ref "R2-USB1") (pin "2") (pinfunction "2_2") (pintype "passive"))
    )
    (net (code "34") (name "Net-(J2-PadB5)") (class "Default")
      (node (ref "J2") (pin "B5") (pinfunction "B5_B5") (pintype "bidirectional"))
      (node (ref "R2-USB") (pin "1") (pinfunction "1_1") (pintype "passive"))
    )
    (net (code "35") (name "Net-(MCP73831-PROG)") (class "Default")
      (node (ref "MCP73831") (pin "5") (pinfunction "PROG_5") (pintype "input"))
      (node (ref "R2_BAT") (pin "2") (pinfunction "2_2") (pintype "passive"))
    )
    (net (code "36") (name "Net-(MCP73831-STAT)") (class "Default")
      (node (ref "MCP73831") (pin "1") (pinfunction "STAT_1") (pintype "output"))
      (node (ref "R1_BAT") (pin "2") (pinfunction "2_2") (pintype "passive"))
    )
    (net (code "37") (name "PREVGH") (class "Default")
      (node (ref "D5") (pin "1") (pinfunction "K_1") (pintype "bidirectional"))
      (node (ref "EPD_C9") (pin "2") (pinfunction "2_2") (pintype "passive"))
      (node (ref "J1") (pin "21") (pinfunction "21_21") (pintype "bidirectional"))
    )
    (net (code "38") (name "PREVGL") (class "Default")
      (node (ref "D4") (pin "2") (pinfunction "A_2") (pintype "bidirectional"))
      (node (ref "EPD_C3") (pin "2") (pinfunction "2_2") (pintype "passive"))
      (node (ref "J1") (pin "23") (pinfunction "23_23") (pintype "bidirectional"))
    )
    (net (code "39") (name "RESE") (class "Default")
      (node (ref "J1") (pin "3") (pinfunction "3_3") (pintype "bidirectional"))
      (node (ref "Q3") (pin "2") (pinfunction "S_2") (pintype "bidirectional"))
      (node (ref "R3") (pin "2") (pinfunction "2_2") (pintype "passive"))
    )
    (net (code "40") (name "RESE'") (class "Default")
      (node (ref "R2") (pin "2") (pinfunction "2_2") (pintype "passive"))
      (node (ref "R3") (pin "1") (pinfunction "1_1") (pintype "passive"))
      (node (ref "SJ1") (pin "2") (pinfunction "2_2") (pintype "passive"))
    )
    (net (code "41") (name "RESET") (class "Default")
      (node (ref "C5") (pin "1") (pinfunction "1_1") (pintype "passive"))
      (node (ref "IC1") (pin "1") (pinfunction "VOUT_1") (pintype "bidirectional"))
      (node (ref "RESET_BUTTON") (pin "3") (pinfunction "3_3") (pintype "passive"))
      (node (ref "RESET_BUTTON") (pin "4") (pinfunction "4_4") (pintype "passive"))
      (node (ref "R_RESET") (pin "1") (pinfunction "1_1") (pintype "passive"))
      (node (ref "U2") (pin "3") (pinfunction "EN_3") (pintype "input"))
    )
    (net (code "42") (name "RTC_RST") (class "Default")
      (node (ref "U2") (pin "16") (pinfunction "IO18_16") (pintype "bidirectional"))
      (node (ref "U3") (pin "4") (pinfunction "~{RST}_4") (pintype "input"))
    )
    (net (code "43") (name "RX") (class "Default")
      (node (ref "TP2") (pin "TP") (pinfunction "TP_TP") (pintype "input"))
      (node (ref "U2") (pin "24") (pinfunction "RXD0/GPIO17_24") (pintype "bidirectional"))
    )
    (net (code "44") (name "SCK") (class "Default")
      (node (ref "D10") (pin "2") (pinfunction "2_2") (pintype "passive"))
      (node (ref "J1") (pin "13") (pinfunction "13_13") (pintype "bidirectional"))
      (node (ref "J4") (pin "P5") (pinfunction "CLK_P5") (pintype "bidirectional"))
      (node (ref "R6") (pin "1") (pinfunction "1_1") (pintype "passive"))
      (node (ref "TP8") (pin "TP") (pinfunction "TP_TP") (pintype "input"))
      (node (ref "U1") (pin "6") (pinfunction "CLK_6") (pintype "input"))
      (node (ref "U2") (pin "6") (pinfunction "IO6_6") (pintype "bidirectional"))
    )
    (net (code "45") (name "SCL") (class "Default")
      (node (ref "J3") (pin "4") (pinfunction "4_4") (pintype "passive"))
      (node (ref "R2_PINH") (pin "1") (pinfunction "1_1") (pintype "passive"))
      (node (ref "SENSOR2") (pin "4") (pinfunction "SCK_4") (pintype "input"))
      (node (ref "U2") (pin "20") (pinfunction "IO22_20") (pintype "bidirectional"))
      (node (ref "U3") (pin "16") (pinfunction "SCL_16") (pintype "input"))
      (node (ref "U4") (pin "7") (pinfunction "SCL_7") (pintype "input"))
    )
    (net (code "46") (name "SDA") (class "Default")
      (node (ref "J3") (pin "3") (pinfunction "3_3") (pintype "passive"))
      (node (ref "R1_PINH") (pin "1") (pinfunction "1_1") (pintype "passive"))
      (node (ref "SENSOR2") (pin "3") (pinfunction "SDI_3") (pintype "bidirectional"))
      (node (ref "U2") (pin "19") (pinfunction "IO21_19") (pintype "bidirectional"))
      (node (ref "U3") (pin "15") (pinfunction "SDA_15") (pintype "bidirectional"))
      (node (ref "U4") (pin "8") (pinfunction "SDA_8") (pintype "bidirectional"))
    )
    (net (code "47") (name "SRC") (class "Default")
      (node (ref "C4") (pin "2") (pinfunction "2_2") (pintype "passive"))
      (node (ref "D5") (pin "2") (pinfunction "A_2") (pintype "bidirectional"))
      (node (ref "L1") (pin "1") (pinfunction "1_1") (pintype "passive"))
      (node (ref "Q3") (pin "3") (pinfunction "D_3") (pintype "bidirectional"))
    )
    (net (code "48") (name "SS_SD") (class "Default")
      (node (ref "D6") (pin "2") (pinfunction "2_2") (pintype "passive"))
      (node (ref "J4") (pin "P2") (pinfunction "CD/DAT3_P2") (pintype "bidirectional"))
      (node (ref "R10") (pin "1") (pinfunction "1_1") (pintype "passive"))
      (node (ref "U2") (pin "4") (pinfunction "IO4_4") (pintype "bidirectional"))
    )
    (net (code "49") (name "TX") (class "Default")
      (node (ref "TP1") (pin "TP") (pinfunction "TP_TP") (pintype "input"))
      (node (ref "U2") (pin "25") (pinfunction "TXD0/GPIO16_25") (pintype "bidirectional"))
    )
    (net (code "50") (name "USB_D+") (class "Default")
      (node (ref "D1") (pin "1") (pinfunction "I/O1_1_1") (pintype "bidirectional"))
      (node (ref "U2") (pin "14") (pinfunction "IO13_14") (pintype "bidirectional"))
    )
    (net (code "51") (name "USB_D-") (class "Default")
      (node (ref "D1") (pin "3") (pinfunction "I/O2_1_3") (pintype "bidirectional"))
      (node (ref "U2") (pin "13") (pinfunction "IO12_13") (pintype "bidirectional"))
    )
    (net (code "52") (name "VBAT") (class "Default")
      (node (ref "C2_BAT") (pin "1") (pinfunction "1_1") (pintype "passive"))
      (node (ref "MCP73831") (pin "3") (pinfunction "VBAT_3") (pintype "power_in"))
      (node (ref "Q1") (pin "3") (pinfunction "D_3") (pintype "bidirectional"))
      (node (ref "TP3") (pin "TP") (pinfunction "TP_TP") (pintype "input"))
      (node (ref "U4") (pin "2") (pinfunction "CELL_2") (pintype "power_in"))
      (node (ref "U4") (pin "3") (pinfunction "VDD_3") (pintype "power_in"))
    )
    (net (code "53") (name "VBUS") (class "Default")
      (node (ref "C1_BAT") (pin "1") (pinfunction "1_1") (pintype "passive"))
      (node (ref "C4_USB") (pin "1") (pinfunction "1_1") (pintype "passive"))
      (node (ref "C5_USB") (pin "1") (pinfunction "1_1") (pintype "passive"))
      (node (ref "CHG_LED") (pin "A") (pinfunction "A_A") (pintype "passive"))
      (node (ref "D1") (pin "5") (pinfunction "VBUS_5") (pintype "bidirectional"))
      (node (ref "D2") (pin "2") (pinfunction "ANODE_2") (pintype "bidirectional"))
      (node (ref "MCP73831") (pin "4") (pinfunction "VIN_4") (pintype "power_in"))
      (node (ref "PFMF.050.1") (pin "2") (pinfunction "2_2") (pintype "passive"))
      (node (ref "Q1") (pin "1") (pinfunction "G_1") (pintype "bidirectional"))
      (node (ref "R1_PWRUSB") (pin "2") (pinfunction "2_2") (pintype "passive"))
      (node (ref "TP14") (pin "TP") (pinfunction "TP_TP") (pintype "input"))
    )
    (net (code "54") (name "VRTC") (class "Default")
      (node (ref "C10_SUPERCAP") (pin "1") (pinfunction "1_1") (pintype "passive"))
      (node (ref "C8") (pin "1") (pinfunction "1_1") (pintype "passive"))
      (node (ref "R_CAPACITOR") (pin "2") (pinfunction "2_2") (pintype "passive"))
      (node (ref "U3") (pin "14") (pinfunction "VBAT_14") (pintype "power_in"))
    )
    (net (code "55") (name "VUSB") (class "Default")
      (node (ref "J2") (pin "A4") (pinfunction "A4_A4") (pintype "bidirectional"))
      (node (ref "J2") (pin "A9") (pinfunction "A9_A9") (pintype "bidirectional"))
      (node (ref "J2") (pin "B4") (pinfunction "B4_B4") (pintype "bidirectional"))
      (node (ref "J2") (pin "B9") (pinfunction "B9_B9") (pintype "bidirectional"))
      (node (ref "PFMF.050.1") (pin "1") (pinfunction "1_1") (pintype "passive"))
    )
    (net (code "56") (name "unconnected-(IC1-NC-Pad4)") (class "Default")
      (node (ref "IC1") (pin "4") (pinfunction "NC_4") (pintype "no_connect"))
    )
    (net (code "57") (name "unconnected-(IC4-NC-Pad4)") (class "Default")
      (node (ref "IC4") (pin "4") (pinfunction "NC_4") (pintype "no_connect"))
    )
    (net (code "58") (name "unconnected-(J1-Pad1)") (class "Default")
      (node (ref "J1") (pin "1") (pinfunction "1_1") (pintype "bidirectional"))
    )
    (net (code "59") (name "unconnected-(J1-Pad6)") (class "Default")
      (node (ref "J1") (pin "6") (pinfunction "6_6") (pintype "bidirectional"))
    )
    (net (code "60") (name "unconnected-(J1-Pad7)") (class "Default")
      (node (ref "J1") (pin "7") (pinfunction "7_7") (pintype "bidirectional"))
    )
    (net (code "61") (name "unconnected-(J2-PadA8)") (class "Default")
      (node (ref "J2") (pin "A8") (pinfunction "A8_A8") (pintype "bidirectional"))
    )
    (net (code "62") (name "unconnected-(J2-PadB8)") (class "Default")
      (node (ref "J2") (pin "B8") (pinfunction "B8_B8") (pintype "bidirectional"))
    )
    (net (code "63") (name "unconnected-(J4-DAT1-PadP8)") (class "Default")
      (node (ref "J4") (pin "P8") (pinfunction "DAT1_P8") (pintype "bidirectional"))
    )
    (net (code "64") (name "unconnected-(J4-DAT2-PadP1)") (class "Default")
      (node (ref "J4") (pin "P1") (pinfunction "DAT2_P1") (pintype "bidirectional"))
    )
    (net (code "65") (name "unconnected-(J4-DETECTION_1-PadS1)") (class "Default")
      (node (ref "J4") (pin "S1") (pinfunction "DETECTION_1_S1") (pintype "bidirectional"))
    )
    (net (code "66") (name "unconnected-(J4-DETECTION_2-PadS2)") (class "Default")
      (node (ref "J4") (pin "S2") (pinfunction "DETECTION_2_S2") (pintype "bidirectional"))
    )
    (net (code "67") (name "unconnected-(U2-NC-Pad22)") (class "Default")
      (node (ref "U2") (pin "22") (pinfunction "NC_22") (pintype "no_connect"))
    )
    (net (code "68") (name "unconnected-(U4-~{ALERT}-Pad5)") (class "Default")
      (node (ref "U4") (pin "5") (pinfunction "~{ALERT}_5") (pintype "output"))
    )
  )
)
